# gateac11.net
KiCad netlist of a schematic drawn in EAGLE
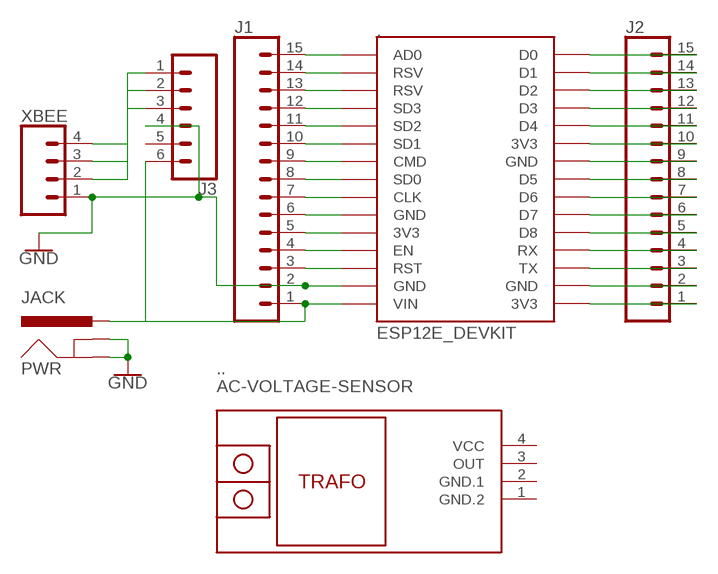
[diagram p0: schematic, sheet 1]

(export (version "E")
  (design (tool "Eeschema 10.0.6"))
  (components
    (comp (ref ".")
      (value "ESP12E_DEVKIT")
      (footprint "eagle-import:ESP12E_DEVKIT")
      (libsource (lib "eagle-import") (part "ESP12E_DEVKIT"))
    )
    (comp (ref "..")
      (value "AC-VOLTAGE-SENSOR")
      (footprint "eagle-import:AC-VOLTAGE-SENSOR")
      (libsource (lib "eagle-import") (part "AC-VOLTAGE-SENSOR"))
    )
    (comp (ref "J1")
      (value "CONN_15")
      (footprint "eagle-import:1X15")
      (libsource (lib "eagle-import") (part "CONN_15"))
    )
    (comp (ref "J2")
      (value "CONN_15")
      (footprint "eagle-import:1X15")
      (libsource (lib "eagle-import") (part "CONN_15"))
    )
    (comp (ref "J3")
      (value "CONN_06SILK_FEMALE_PTH")
      (footprint "eagle-import:1X06")
      (libsource (lib "eagle-import") (part "CONN_06SILK_FEMALE_PTH"))
    )
    (comp (ref "PWR")
      (value "JACK")
      (footprint "eagle-import:POWER_JACK_PTH_BREAD")
      (libsource (lib "eagle-import") (part "POWER_JACKPTH_BREAD"))
    )
    (comp (ref "XBEE")
      (value "CONN_04")
      (footprint "eagle-import:1X04")
      (libsource (lib "eagle-import") (part "CONN_04"))
    )
  )
  (nets
    (net (code "1") (name "/GND.1") (class "Default")
      (node (ref "..") (pin "2") (pinfunction "GND.1_2") (pintype "power_in"))
    )
    (net (code "2") (name "/GND.2") (class "Default")
      (node (ref "..") (pin "1") (pinfunction "GND.2_1") (pintype "power_in"))
    )
    (net (code "3") (name "/VCC") (class "Default")
      (node (ref "..") (pin "4") (pinfunction "VCC_4") (pintype "power_in"))
    )
    (net (code "4") (name "GND") (class "Default")
      (node (ref ".") (pin "GND@1") (pinfunction "GND_GND@1") (pintype "bidirectional"))
      (node (ref "J1") (pin "2") (pinfunction "2_2") (pintype "passive"))
      (node (ref "J3") (pin "4") (pinfunction "4_4") (pintype "passive"))
      (node (ref "PWR") (pin "GND") (pinfunction "GND_GND") (pintype "bidirectional"))
      (node (ref "PWR") (pin "GNDBREAK") (pinfunction "GNDBREAK_GNDBREAK") (pintype "bidirectional"))
      (node (ref "XBEE") (pin "1") (pinfunction "1_1") (pintype "passive"))
    )
    (net (code "5") (name "Net-(.-3V3-Pad3V3@0)") (class "Default")
      (node (ref ".") (pin "3V3@0") (pinfunction "3V3_3V3@0") (pintype "bidirectional"))
      (node (ref "J1") (pin "5") (pinfunction "5_5") (pintype "passive"))
    )
    (net (code "6") (name "Net-(.-3V3-Pad3V3@1)") (class "Default")
      (node (ref ".") (pin "3V3@1") (pinfunction "3V3_3V3@1") (pintype "bidirectional"))
      (node (ref "J2") (pin "10") (pinfunction "10_10") (pintype "passive"))
    )
    (net (code "7") (name "Net-(.-3V3-Pad3V3@2)") (class "Default")
      (node (ref ".") (pin "3V3@2") (pinfunction "3V3_3V3@2") (pintype "bidirectional"))
      (node (ref "J2") (pin "1") (pinfunction "1_1") (pintype "passive"))
    )
    (net (code "8") (name "Net-(.-GND-PadGND@0)") (class "Default")
      (node (ref ".") (pin "GND@0") (pinfunction "GND_GND@0") (pintype "bidirectional"))
      (node (ref "J1") (pin "6") (pinfunction "6_6") (pintype "passive"))
    )
    (net (code "9") (name "Net-(.-GND-PadGND@2)") (class "Default")
      (node (ref ".") (pin "GND@2") (pinfunction "GND_GND@2") (pintype "bidirectional"))
      (node (ref "J2") (pin "9") (pinfunction "9_9") (pintype "passive"))
    )
    (net (code "10") (name "Net-(.-GND-PadGND@3)") (class "Default")
      (node (ref ".") (pin "GND@3") (pinfunction "GND_GND@3") (pintype "bidirectional"))
      (node (ref "J2") (pin "2") (pinfunction "2_2") (pintype "passive"))
    )
    (net (code "11") (name "Net-(.-PadAD0)") (class "Default")
      (node (ref ".") (pin "AD0") (pinfunction "AD0_AD0") (pintype "bidirectional"))
      (node (ref "J1") (pin "15") (pinfunction "15_15") (pintype "passive"))
    )
    (net (code "12") (name "Net-(.-PadCLK)") (class "Default")
      (node (ref ".") (pin "CLK") (pinfunction "CLK_CLK") (pintype "bidirectional"))
      (node (ref "J1") (pin "7") (pinfunction "7_7") (pintype "passive"))
    )
    (net (code "13") (name "Net-(.-PadCMD)") (class "Default")
      (node (ref ".") (pin "CMD") (pinfunction "CMD_CMD") (pintype "bidirectional"))
      (node (ref "J1") (pin "9") (pinfunction "9_9") (pintype "passive"))
    )
    (net (code "14") (name "Net-(.-PadD0)") (class "Default")
      (node (ref ".") (pin "D0") (pinfunction "D0_D0") (pintype "bidirectional"))
      (node (ref "J2") (pin "15") (pinfunction "15_15") (pintype "passive"))
    )
    (net (code "15") (name "Net-(.-PadD1)") (class "Default")
      (node (ref ".") (pin "D1") (pinfunction "D1_D1") (pintype "bidirectional"))
      (node (ref "J2") (pin "14") (pinfunction "14_14") (pintype "passive"))
    )
    (net (code "16") (name "Net-(.-PadD2)") (class "Default")
      (node (ref ".") (pin "D2") (pinfunction "D2_D2") (pintype "bidirectional"))
      (node (ref "J2") (pin "13") (pinfunction "13_13") (pintype "passive"))
    )
    (net (code "17") (name "Net-(.-PadD3)") (class "Default")
      (node (ref ".") (pin "D3") (pinfunction "D3_D3") (pintype "bidirectional"))
      (node (ref "J2") (pin "12") (pinfunction "12_12") (pintype "passive"))
    )
    (net (code "18") (name "Net-(.-PadD4)") (class "Default")
      (node (ref ".") (pin "D4") (pinfunction "D4_D4") (pintype "bidirectional"))
      (node (ref "J2") (pin "11") (pinfunction "11_11") (pintype "passive"))
    )
    (net (code "19") (name "Net-(.-PadD5)") (class "Default")
      (node (ref ".") (pin "D5") (pinfunction "D5_D5") (pintype "bidirectional"))
      (node (ref "J2") (pin "8") (pinfunction "8_8") (pintype "passive"))
    )
    (net (code "20") (name "Net-(.-PadD6)") (class "Default")
      (node (ref ".") (pin "D6") (pinfunction "D6_D6") (pintype "bidirectional"))
      (node (ref "J2") (pin "7") (pinfunction "7_7") (pintype "passive"))
    )
    (net (code "21") (name "Net-(.-PadD7)") (class "Default")
      (node (ref ".") (pin "D7") (pinfunction "D7_D7") (pintype "bidirectional"))
      (node (ref "J2") (pin "6") (pinfunction "6_6") (pintype "passive"))
    )
    (net (code "22") (name "Net-(.-PadD8)") (class "Default")
      (node (ref ".") (pin "D8") (pinfunction "D8_D8") (pintype "bidirectional"))
      (node (ref "J2") (pin "5") (pinfunction "5_5") (pintype "passive"))
    )
    (net (code "23") (name "Net-(.-PadEN)") (class "Default")
      (node (ref ".") (pin "EN") (pinfunction "EN_EN") (pintype "bidirectional"))
      (node (ref "J1") (pin "4") (pinfunction "4_4") (pintype "passive"))
    )
    (net (code "24") (name "Net-(.-PadRST)") (class "Default")
      (node (ref ".") (pin "RST") (pinfunction "RST_RST") (pintype "bidirectional"))
      (node (ref "J1") (pin "3") (pinfunction "3_3") (pintype "passive"))
    )
    (net (code "25") (name "Net-(.-PadRX)") (class "Default")
      (node (ref ".") (pin "RX") (pinfunction "RX_RX") (pintype "bidirectional"))
      (node (ref "J2") (pin "4") (pinfunction "4_4") (pintype "passive"))
    )
    (net (code "26") (name "Net-(.-PadSD0)") (class "Default")
      (node (ref ".") (pin "SD0") (pinfunction "SD0_SD0") (pintype "bidirectional"))
      (node (ref "J1") (pin "8") (pinfunction "8_8") (pintype "passive"))
    )
    (net (code "27") (name "Net-(.-PadSD1)") (class "Default")
      (node (ref ".") (pin "SD1") (pinfunction "SD1_SD1") (pintype "bidirectional"))
      (node (ref "J1") (pin "10") (pinfunction "10_10") (pintype "passive"))
    )
    (net (code "28") (name "Net-(.-PadSD2)") (class "Default")
      (node (ref ".") (pin "SD2") (pinfunction "SD2_SD2") (pintype "bidirectional"))
      (node (ref "J1") (pin "11") (pinfunction "11_11") (pintype "passive"))
    )
    (net (code "29") (name "Net-(.-PadSD3)") (class "Default")
      (node (ref ".") (pin "SD3") (pinfunction "SD3_SD3") (pintype "bidirectional"))
      (node (ref "J1") (pin "12") (pinfunction "12_12") (pintype "passive"))
    )
    (net (code "30") (name "Net-(.-PadTX)") (class "Default")
      (node (ref ".") (pin "TX") (pinfunction "TX_TX") (pintype "bidirectional"))
      (node (ref "J2") (pin "3") (pinfunction "3_3") (pintype "passive"))
    )
    (net (code "31") (name "Net-(.-PadVIN)") (class "Default")
      (node (ref ".") (pin "VIN") (pinfunction "VIN_VIN") (pintype "bidirectional"))
      (node (ref "J1") (pin "1") (pinfunction "1_1") (pintype "passive"))
      (node (ref "J3") (pin "6") (pinfunction "6_6") (pintype "passive"))
      (node (ref "PWR") (pin "PWR") (pinfunction "PWR_PWR") (pintype "bidirectional"))
    )
    (net (code "32") (name "Net-(.-RSV-PadRSV@0)") (class "Default")
      (node (ref ".") (pin "RSV@0") (pinfunction "RSV_RSV@0") (pintype "bidirectional"))
      (node (ref "J1") (pin "14") (pinfunction "14_14") (pintype "passive"))
    )
    (net (code "33") (name "Net-(.-RSV-PadRSV@1)") (class "Default")
      (node (ref ".") (pin "RSV@1") (pinfunction "RSV_RSV@1") (pintype "bidirectional"))
      (node (ref "J1") (pin "13") (pinfunction "13_13") (pintype "passive"))
    )
    (net (code "34") (name "Net-(J3-Pad1)") (class "Default")
      (node (ref "J3") (pin "1") (pinfunction "1_1") (pintype "passive"))
      (node (ref "XBEE") (pin "4") (pinfunction "4_4") (pintype "passive"))
    )
    (net (code "35") (name "Net-(J3-Pad2)") (class "Default")
      (node (ref "J3") (pin "2") (pinfunction "2_2") (pintype "passive"))
      (node (ref "XBEE") (pin "3") (pinfunction "3_3") (pintype "passive"))
    )
    (net (code "36") (name "Net-(J3-Pad3)") (class "Default")
      (node (ref "J3") (pin "3") (pinfunction "3_3") (pintype "passive"))
      (node (ref "XBEE") (pin "2") (pinfunction "2_2") (pintype "passive"))
    )
    (net (code "37") (name "unconnected-(..-OUT-Pad3)") (class "Default")
      (node (ref "..") (pin "3") (pinfunction "OUT_3") (pintype "output"))
    )
    (net (code "38") (name "unconnected-(J3-Pad5)") (class "Default")
      (node (ref "J3") (pin "5") (pinfunction "5_5") (pintype "passive"))
    )
  )
)
